# HB-UNI-Sen-PM_SHT31_Board_v2.net
KiCad netlist of a schematic drawn in EAGLE
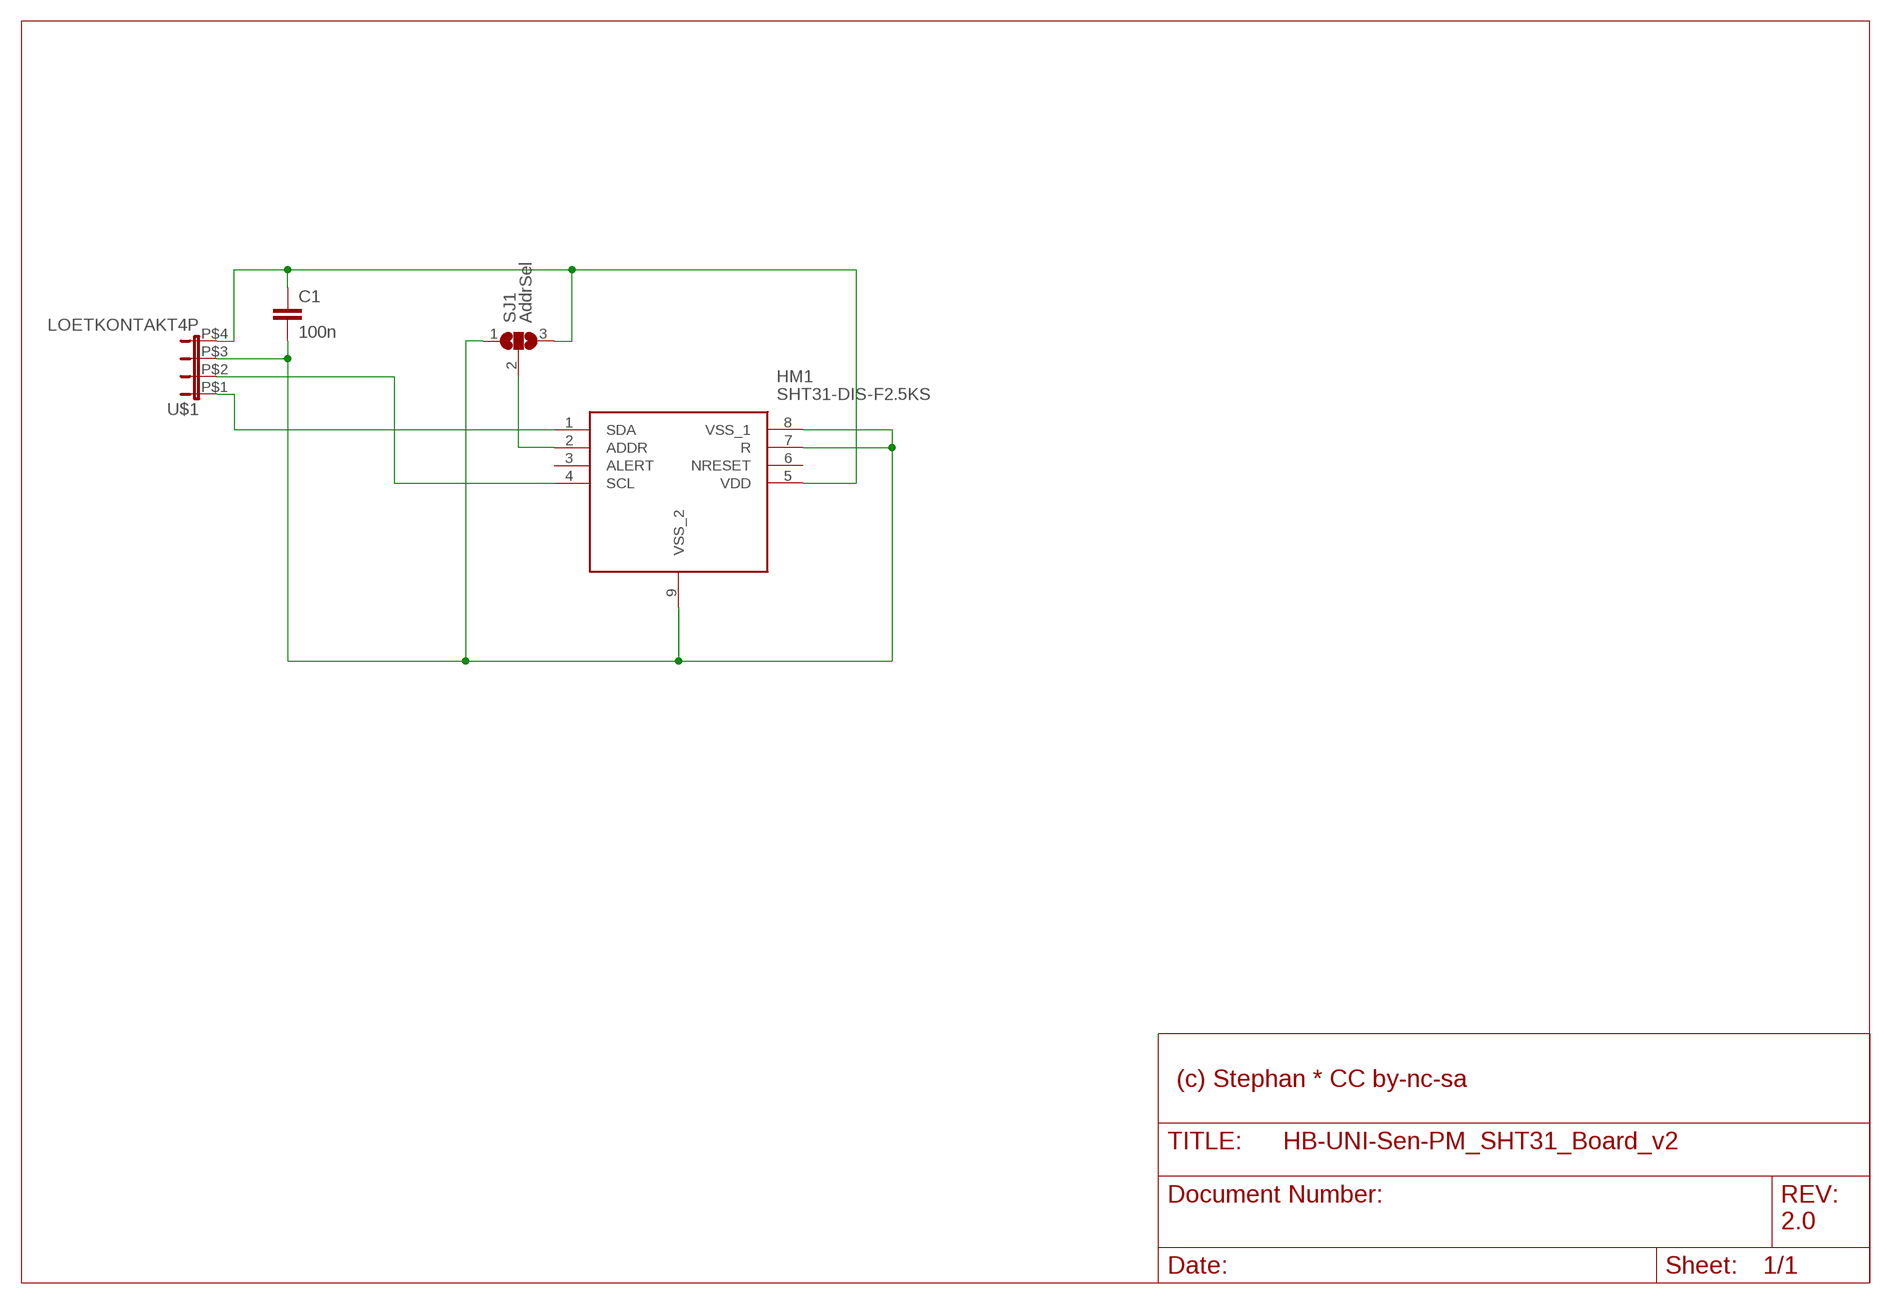
[diagram p0: schematic, sheet 1]

(export (version "E")
  (design (tool "Eeschema 10.0.6"))
  (components
    (comp (ref "C1")
      (value "100n")
      (footprint "eagle-import:C0603K")
      (libsource (lib "eagle-import") (part "C-EUC0603K"))
    )
    (comp (ref "HM1")
      (value "SHT31-DIS-F2.5KS")
      (footprint "eagle-import:SON50P250X250X90-9N")
      (fields
        (field (name "MANUFACTURER_PART_NUMBER") "SHT31-DIS-F2.5kS")
        (field (name "MOUSER_PART_NUMBER") "403-SHT31-DIS-F")
      )
      (libsource (lib "eagle-import") (part "SHT31-DIS-F2.5KS"))
    )
    (comp (ref "SJ1")
      (value "AddrSel")
      (footprint "eagle-import:SJ_2")
      (libsource (lib "eagle-import") (part "SJ2W"))
    )
    (comp (ref "U$1")
      (value "LOETKONTAKT4P")
      (footprint "eagle-import:LOETKONTAKT4P")
      (libsource (lib "eagle-import") (part "LOETKONTAKT4P"))
    )
  )
  (nets
    (net (code "1") (name "Net-(HM1-ADDR)") (class "Default")
      (node (ref "HM1") (pin "2") (pinfunction "ADDR_2") (pintype "input"))
      (node (ref "SJ1") (pin "2") (pinfunction "2_2") (pintype "passive"))
    )
    (net (code "2") (name "Net-(HM1-R)") (class "Default")
      (node (ref "C1") (pin "2") (pinfunction "2_2") (pintype "passive"))
      (node (ref "HM1") (pin "7") (pinfunction "R_7") (pintype "bidirectional"))
      (node (ref "HM1") (pin "8") (pinfunction "VSS_1_8") (pintype "power_in"))
      (node (ref "HM1") (pin "9") (pinfunction "VSS_2_9") (pintype "power_in"))
      (node (ref "SJ1") (pin "1") (pinfunction "1_1") (pintype "passive"))
      (node (ref "U$1") (pin "P$3") (pinfunction "3_P$3") (pintype "passive"))
    )
    (net (code "3") (name "Net-(HM1-SCL)") (class "Default")
      (node (ref "HM1") (pin "4") (pinfunction "SCL_4") (pintype "bidirectional"))
      (node (ref "U$1") (pin "P$2") (pinfunction "2_P$2") (pintype "passive"))
    )
    (net (code "4") (name "Net-(HM1-SDA)") (class "Default")
      (node (ref "HM1") (pin "1") (pinfunction "SDA_1") (pintype "bidirectional"))
      (node (ref "U$1") (pin "P$1") (pinfunction "1_P$1") (pintype "passive"))
    )
    (net (code "5") (name "Net-(HM1-VDD)") (class "Default")
      (node (ref "C1") (pin "1") (pinfunction "1_1") (pintype "passive"))
      (node (ref "HM1") (pin "5") (pinfunction "VDD_5") (pintype "power_in"))
      (node (ref "SJ1") (pin "3") (pinfunction "3_3") (pintype "passive"))
      (node (ref "U$1") (pin "P$4") (pinfunction "4_P$4") (pintype "passive"))
    )
    (net (code "6") (name "unconnected-(HM1-ALERT-Pad3)") (class "Default")
      (node (ref "HM1") (pin "3") (pinfunction "ALERT_3") (pintype "output"))
    )
    (net (code "7") (name "unconnected-(HM1-NRESET-Pad6)") (class "Default")
      (node (ref "HM1") (pin "6") (pinfunction "NRESET_6") (pintype "input"))
    )
  )
)
